# LEDTestBrd.net
KiCad netlist of a schematic drawn in EAGLE
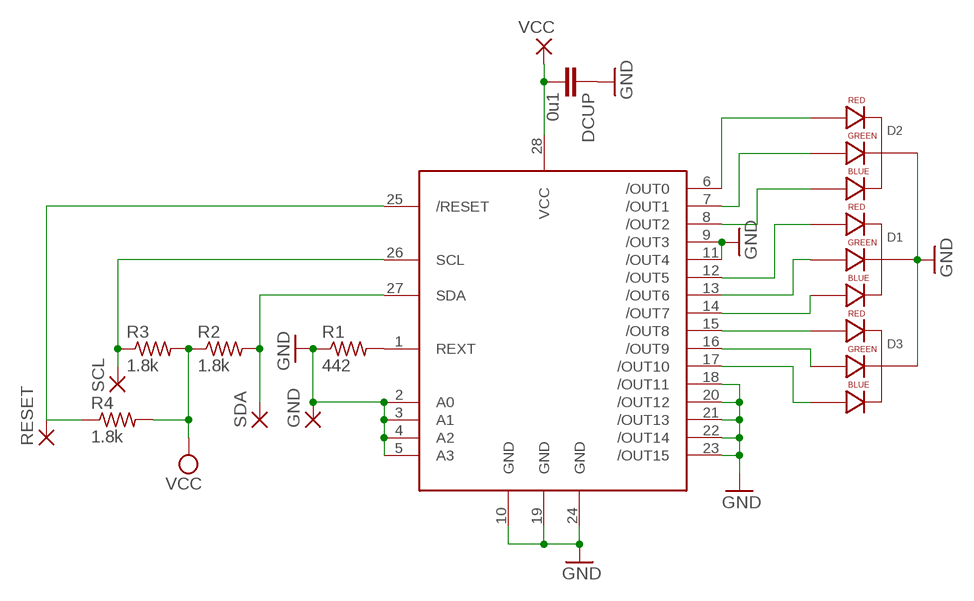
[diagram p0: schematic, sheet 1]

(export (version "E")
  (design (tool "Eeschema 10.0.6"))
  (components
    (comp (ref "D1")
      (value "LED-RGB-CC-THRUCLEAR")
      (footprint "eagle-import:LED-RGB-THRU")
      (libsource (lib "eagle-import") (part "LED-RGB-CC-THRUCLEAR"))
    )
    (comp (ref "D2")
      (value "LED-RGB-CC-THRUCLEAR")
      (footprint "eagle-import:LED-RGB-THRU")
      (libsource (lib "eagle-import") (part "LED-RGB-CC-THRUCLEAR"))
    )
    (comp (ref "D3")
      (value "LED-RGB-CC-THRUCLEAR")
      (footprint "eagle-import:LED-RGB-THRU")
      (libsource (lib "eagle-import") (part "LED-RGB-CC-THRUCLEAR"))
    )
    (comp (ref "DCUP")
      (value "0u1")
      (footprint "eagle-import:0402-CAP")
      (libsource (lib "eagle-import") (part "CAP0402-CAP"))
    )
    (comp (ref "GND")
      (value "2,15/1,0")
      (footprint "eagle-import:2,15_1,0")
      (libsource (lib "eagle-import") (part "2,15/1,0"))
    )
    (comp (ref "R1")
      (value "442")
      (footprint "eagle-import:R0402")
      (libsource (lib "eagle-import") (part "R-US_R0402"))
    )
    (comp (ref "R2")
      (value "1.8k")
      (footprint "eagle-import:R0402")
      (libsource (lib "eagle-import") (part "R-US_R0402"))
    )
    (comp (ref "R3")
      (value "1.8k")
      (footprint "eagle-import:R0402")
      (libsource (lib "eagle-import") (part "R-US_R0402"))
    )
    (comp (ref "R4")
      (value "1.8k")
      (footprint "eagle-import:R0402")
      (libsource (lib "eagle-import") (part "R-US_R0402"))
    )
    (comp (ref "RESET")
      (value "2,15/1,0")
      (footprint "eagle-import:2,15_1,0")
      (libsource (lib "eagle-import") (part "2,15/1,0"))
    )
    (comp (ref "SCL")
      (value "2,15/1,0")
      (footprint "eagle-import:2,15_1,0")
      (libsource (lib "eagle-import") (part "2,15/1,0"))
    )
    (comp (ref "SDA")
      (value "2,15/1,0")
      (footprint "eagle-import:2,15_1,0")
      (libsource (lib "eagle-import") (part "2,15/1,0"))
    )
    (comp (ref "U$1")
      (value "TLC59116")
      (footprint "eagle-import:TSSOP28")
      (libsource (lib "eagle-import") (part "TLC59116"))
    )
    (comp (ref "VCC")
      (value "2,15/1,0")
      (footprint "eagle-import:2,15_1,0")
      (libsource (lib "eagle-import") (part "2,15/1,0"))
    )
  )
  (nets
    (net (code "1") (name "GND") (class "Default")
      (node (ref "D1") (pin "2") (pinfunction "CATHODE_2") (pintype "bidirectional"))
      (node (ref "D2") (pin "2") (pinfunction "CATHODE_2") (pintype "bidirectional"))
      (node (ref "D3") (pin "2") (pinfunction "CATHODE_2") (pintype "bidirectional"))
      (node (ref "DCUP") (pin "1") (pinfunction "1_1") (pintype "passive"))
      (node (ref "GND") (pin "1") (pinfunction "P_1") (pintype "passive"))
      (node (ref "R1") (pin "1") (pinfunction "1_1") (pintype "passive"))
      (node (ref "U$1") (pin "10") (pinfunction "GND_10") (pintype "bidirectional"))
      (node (ref "U$1") (pin "11") (pinfunction "/OUT4_11") (pintype "bidirectional"))
      (node (ref "U$1") (pin "18") (pinfunction "/OUT11_18") (pintype "bidirectional"))
      (node (ref "U$1") (pin "19") (pinfunction "GND_19") (pintype "bidirectional"))
      (node (ref "U$1") (pin "2") (pinfunction "A0_2") (pintype "bidirectional"))
      (node (ref "U$1") (pin "20") (pinfunction "/OUT12_20") (pintype "bidirectional"))
      (node (ref "U$1") (pin "21") (pinfunction "/OUT13_21") (pintype "bidirectional"))
      (node (ref "U$1") (pin "22") (pinfunction "/OUT14_22") (pintype "bidirectional"))
      (node (ref "U$1") (pin "23") (pinfunction "/OUT15_23") (pintype "bidirectional"))
      (node (ref "U$1") (pin "24") (pinfunction "GND_24") (pintype "bidirectional"))
      (node (ref "U$1") (pin "3") (pinfunction "A1_3") (pintype "bidirectional"))
      (node (ref "U$1") (pin "4") (pinfunction "A2_4") (pintype "bidirectional"))
      (node (ref "U$1") (pin "5") (pinfunction "A3_5") (pintype "bidirectional"))
      (node (ref "U$1") (pin "9") (pinfunction "/OUT3_9") (pintype "bidirectional"))
    )
    (net (code "2") (name "Net-(D1-BLUE_CATHODE)") (class "Default")
      (node (ref "D1") (pin "4") (pinfunction "BLUE_CATHODE_4") (pintype "bidirectional"))
      (node (ref "U$1") (pin "14") (pinfunction "/OUT7_14") (pintype "bidirectional"))
    )
    (net (code "3") (name "Net-(D1-GREEN_CATHODE)") (class "Default")
      (node (ref "D1") (pin "3") (pinfunction "GREEN_CATHODE_3") (pintype "bidirectional"))
      (node (ref "U$1") (pin "13") (pinfunction "/OUT6_13") (pintype "bidirectional"))
    )
    (net (code "4") (name "Net-(D1-RED_CATHODE)") (class "Default")
      (node (ref "D1") (pin "1") (pinfunction "RED_CATHODE_1") (pintype "bidirectional"))
      (node (ref "U$1") (pin "12") (pinfunction "/OUT5_12") (pintype "bidirectional"))
    )
    (net (code "5") (name "Net-(D2-BLUE_CATHODE)") (class "Default")
      (node (ref "D2") (pin "4") (pinfunction "BLUE_CATHODE_4") (pintype "bidirectional"))
      (node (ref "U$1") (pin "8") (pinfunction "/OUT2_8") (pintype "bidirectional"))
    )
    (net (code "6") (name "Net-(D2-GREEN_CATHODE)") (class "Default")
      (node (ref "D2") (pin "3") (pinfunction "GREEN_CATHODE_3") (pintype "bidirectional"))
      (node (ref "U$1") (pin "7") (pinfunction "/OUT1_7") (pintype "bidirectional"))
    )
    (net (code "7") (name "Net-(D2-RED_CATHODE)") (class "Default")
      (node (ref "D2") (pin "1") (pinfunction "RED_CATHODE_1") (pintype "bidirectional"))
      (node (ref "U$1") (pin "6") (pinfunction "/OUT0_6") (pintype "bidirectional"))
    )
    (net (code "8") (name "Net-(D3-BLUE_CATHODE)") (class "Default")
      (node (ref "D3") (pin "4") (pinfunction "BLUE_CATHODE_4") (pintype "bidirectional"))
      (node (ref "U$1") (pin "17") (pinfunction "/OUT10_17") (pintype "bidirectional"))
    )
    (net (code "9") (name "Net-(D3-GREEN_CATHODE)") (class "Default")
      (node (ref "D3") (pin "3") (pinfunction "GREEN_CATHODE_3") (pintype "bidirectional"))
      (node (ref "U$1") (pin "16") (pinfunction "/OUT9_16") (pintype "bidirectional"))
    )
    (net (code "10") (name "Net-(D3-RED_CATHODE)") (class "Default")
      (node (ref "D3") (pin "1") (pinfunction "RED_CATHODE_1") (pintype "bidirectional"))
      (node (ref "U$1") (pin "15") (pinfunction "/OUT8_15") (pintype "bidirectional"))
    )
    (net (code "11") (name "Net-(RESET-P)") (class "Default")
      (node (ref "R4") (pin "1") (pinfunction "1_1") (pintype "passive"))
      (node (ref "RESET") (pin "1") (pinfunction "P_1") (pintype "passive"))
      (node (ref "U$1") (pin "25") (pinfunction "/RESET_25") (pintype "bidirectional"))
    )
    (net (code "12") (name "Net-(SCL-P)") (class "Default")
      (node (ref "R3") (pin "1") (pinfunction "1_1") (pintype "passive"))
      (node (ref "SCL") (pin "1") (pinfunction "P_1") (pintype "passive"))
      (node (ref "U$1") (pin "26") (pinfunction "SCL_26") (pintype "bidirectional"))
    )
    (net (code "13") (name "Net-(SDA-P)") (class "Default")
      (node (ref "R2") (pin "2") (pinfunction "2_2") (pintype "passive"))
      (node (ref "SDA") (pin "1") (pinfunction "P_1") (pintype "passive"))
      (node (ref "U$1") (pin "27") (pinfunction "SDA_27") (pintype "bidirectional"))
    )
    (net (code "14") (name "Net-(U$1-REXT)") (class "Default")
      (node (ref "R1") (pin "2") (pinfunction "2_2") (pintype "passive"))
      (node (ref "U$1") (pin "1") (pinfunction "REXT_1") (pintype "bidirectional"))
    )
    (net (code "15") (name "VCC") (class "Default")
      (node (ref "DCUP") (pin "2") (pinfunction "2_2") (pintype "passive"))
      (node (ref "R2") (pin "1") (pinfunction "1_1") (pintype "passive"))
      (node (ref "R3") (pin "2") (pinfunction "2_2") (pintype "passive"))
      (node (ref "R4") (pin "2") (pinfunction "2_2") (pintype "passive"))
      (node (ref "U$1") (pin "28") (pinfunction "VCC_28") (pintype "bidirectional"))
      (node (ref "VCC") (pin "1") (pinfunction "P_1") (pintype "passive"))
    )
  )
)
